# oven-controller-v3.net
KiCad netlist of a schematic drawn in EAGLE
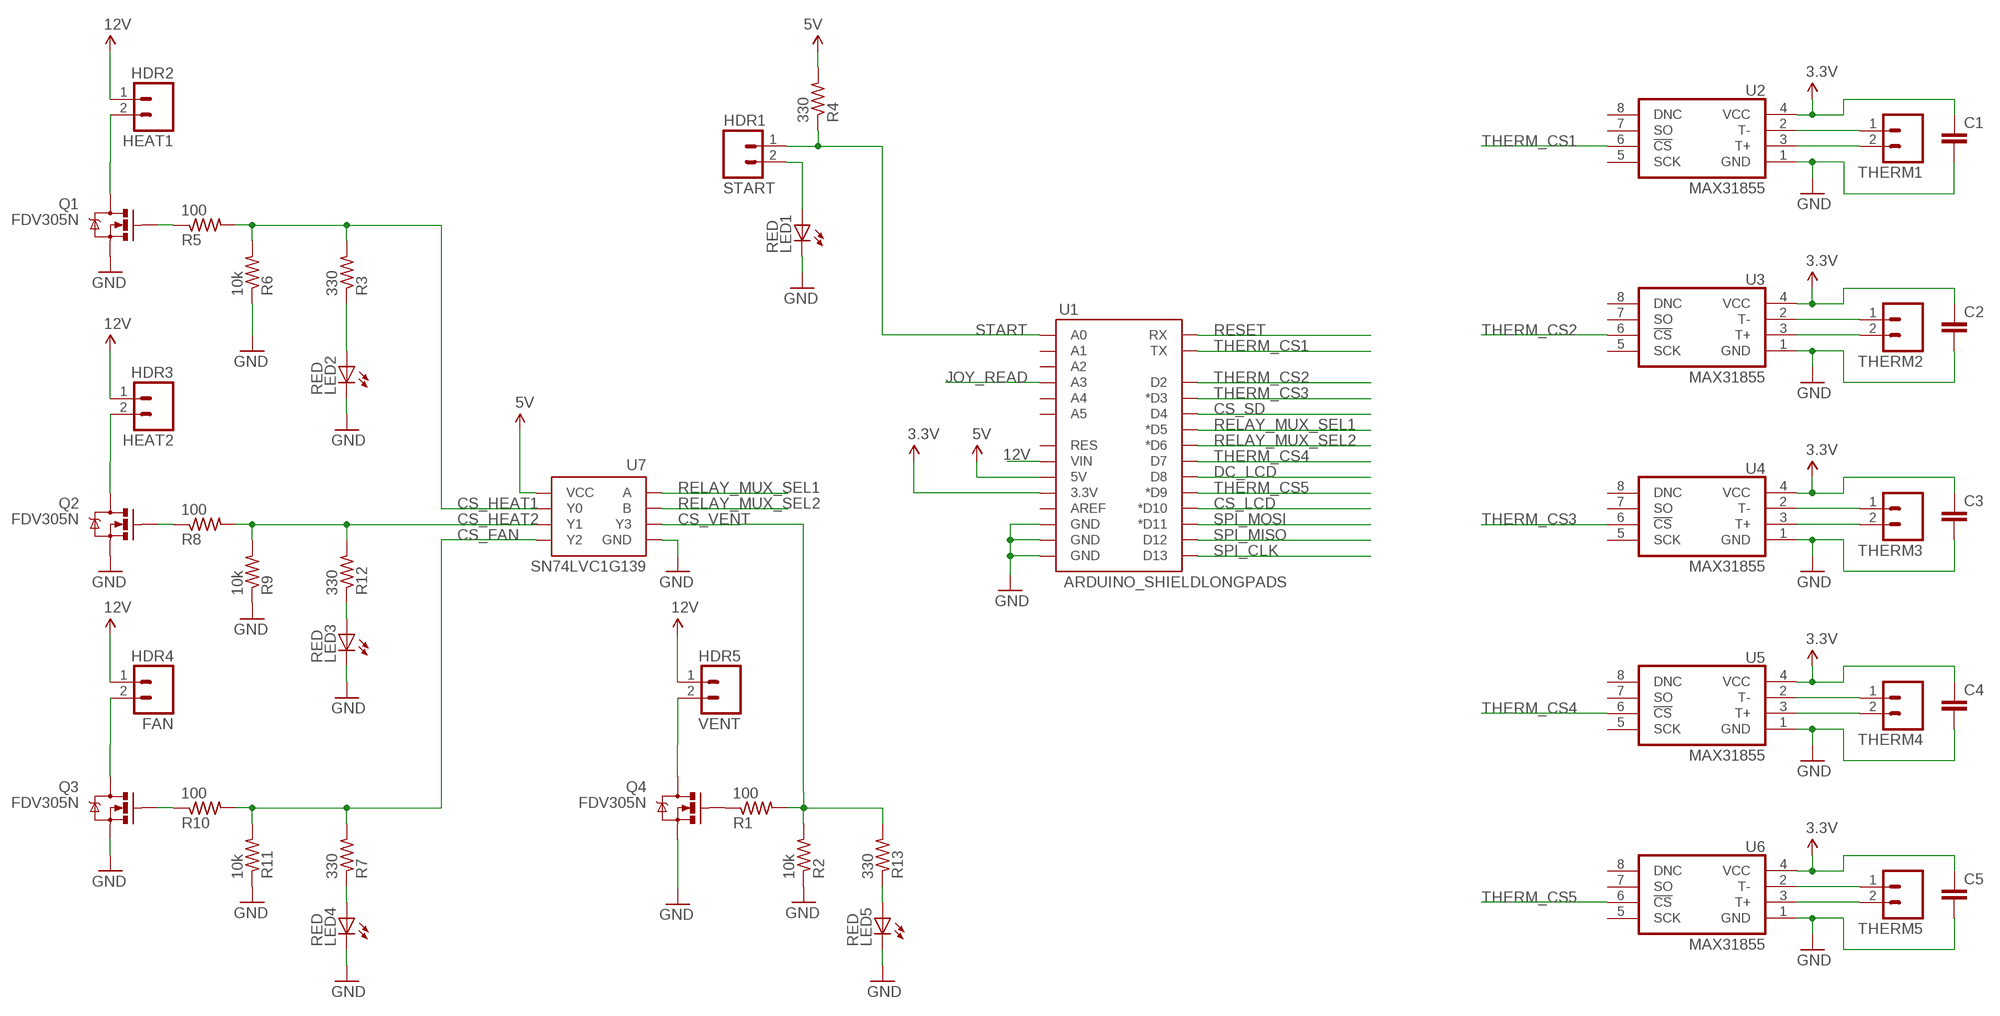
[diagram p0: schematic, sheet 1]

(export (version "E")
  (design (tool "Eeschema 10.0.6"))
  (components
    (comp (ref "C1")
      (value "C-EUC0603K")
      (footprint "eagle-import:C0603K")
      (libsource (lib "eagle-import") (part "C-EUC0603K"))
    )
    (comp (ref "C2")
      (value "C-EUC0603K")
      (footprint "eagle-import:C0603K")
      (libsource (lib "eagle-import") (part "C-EUC0603K"))
    )
    (comp (ref "C3")
      (value "C-EUC0603K")
      (footprint "eagle-import:C0603K")
      (libsource (lib "eagle-import") (part "C-EUC0603K"))
    )
    (comp (ref "C4")
      (value "C-EUC0603K")
      (footprint "eagle-import:C0603K")
      (libsource (lib "eagle-import") (part "C-EUC0603K"))
    )
    (comp (ref "C5")
      (value "C-EUC0603K")
      (footprint "eagle-import:C0603K")
      (libsource (lib "eagle-import") (part "C-EUC0603K"))
    )
    (comp (ref "FAN")
      (value "HDR4")
      (footprint "eagle-import:SCREWTERMINAL-3.5MM-2_LOCK")
      (libsource (lib "eagle-import") (part "M023.5MM_LOCK"))
    )
    (comp (ref "HEAT1")
      (value "HDR2")
      (footprint "eagle-import:SCREWTERMINAL-3.5MM-2_LOCK")
      (libsource (lib "eagle-import") (part "M023.5MM_LOCK"))
    )
    (comp (ref "HEAT2")
      (value "HDR3")
      (footprint "eagle-import:SCREWTERMINAL-3.5MM-2_LOCK")
      (libsource (lib "eagle-import") (part "M023.5MM_LOCK"))
    )
    (comp (ref "LED1")
      (value "RED")
      (footprint "eagle-import:LED-0603")
      (libsource (lib "eagle-import") (part "LED0603"))
    )
    (comp (ref "LED2")
      (value "RED")
      (footprint "eagle-import:LED-0603")
      (libsource (lib "eagle-import") (part "LED0603"))
    )
    (comp (ref "LED3")
      (value "RED")
      (footprint "eagle-import:LED-0603")
      (libsource (lib "eagle-import") (part "LED0603"))
    )
    (comp (ref "LED4")
      (value "RED")
      (footprint "eagle-import:LED-0603")
      (libsource (lib "eagle-import") (part "LED0603"))
    )
    (comp (ref "LED5")
      (value "RED")
      (footprint "eagle-import:LED-0603")
      (libsource (lib "eagle-import") (part "LED0603"))
    )
    (comp (ref "Q1")
      (value "FDV305N")
      (footprint "eagle-import:SOT23-3")
      (libsource (lib "eagle-import") (part "MOSFET-NCHANNELSMD"))
    )
    (comp (ref "Q2")
      (value "FDV305N")
      (footprint "eagle-import:SOT23-3")
      (libsource (lib "eagle-import") (part "MOSFET-NCHANNELSMD"))
    )
    (comp (ref "Q3")
      (value "FDV305N")
      (footprint "eagle-import:SOT23-3")
      (libsource (lib "eagle-import") (part "MOSFET-NCHANNELSMD"))
    )
    (comp (ref "Q4")
      (value "FDV305N")
      (footprint "eagle-import:SOT23-3")
      (libsource (lib "eagle-import") (part "MOSFET-NCHANNELSMD"))
    )
    (comp (ref "R1")
      (value "100")
      (footprint "eagle-import:0603-C-NOSILK")
      (libsource (lib "eagle-import") (part "R-US_0603-C-NOSILK"))
    )
    (comp (ref "R2")
      (value "10k")
      (footprint "eagle-import:0603-C-NOSILK")
      (libsource (lib "eagle-import") (part "R-US_0603-C-NOSILK"))
    )
    (comp (ref "R3")
      (value "330")
      (footprint "eagle-import:0603-C-NOSILK")
      (libsource (lib "eagle-import") (part "R-US_0603-C-NOSILK"))
    )
    (comp (ref "R4")
      (value "330")
      (footprint "eagle-import:0603-C-NOSILK")
      (libsource (lib "eagle-import") (part "R-US_0603-C-NOSILK"))
    )
    (comp (ref "R5")
      (value "100")
      (footprint "eagle-import:0603-C-NOSILK")
      (libsource (lib "eagle-import") (part "R-US_0603-C-NOSILK"))
    )
    (comp (ref "R6")
      (value "10k")
      (footprint "eagle-import:0603-C-NOSILK")
      (libsource (lib "eagle-import") (part "R-US_0603-C-NOSILK"))
    )
    (comp (ref "R7")
      (value "330")
      (footprint "eagle-import:0603-C-NOSILK")
      (libsource (lib "eagle-import") (part "R-US_0603-C-NOSILK"))
    )
    (comp (ref "R8")
      (value "100")
      (footprint "eagle-import:0603-C-NOSILK")
      (libsource (lib "eagle-import") (part "R-US_0603-C-NOSILK"))
    )
    (comp (ref "R9")
      (value "10k")
      (footprint "eagle-import:0603-C-NOSILK")
      (libsource (lib "eagle-import") (part "R-US_0603-C-NOSILK"))
    )
    (comp (ref "R10")
      (value "100")
      (footprint "eagle-import:0603-C-NOSILK")
      (libsource (lib "eagle-import") (part "R-US_0603-C-NOSILK"))
    )
    (comp (ref "R11")
      (value "10k")
      (footprint "eagle-import:0603-C-NOSILK")
      (libsource (lib "eagle-import") (part "R-US_0603-C-NOSILK"))
    )
    (comp (ref "R12")
      (value "330")
      (footprint "eagle-import:0603-C-NOSILK")
      (libsource (lib "eagle-import") (part "R-US_0603-C-NOSILK"))
    )
    (comp (ref "R13")
      (value "330")
      (footprint "eagle-import:0603-C-NOSILK")
      (libsource (lib "eagle-import") (part "R-US_0603-C-NOSILK"))
    )
    (comp (ref "START")
      (value "HDR1")
      (footprint "eagle-import:SCREWTERMINAL-3.5MM-2_LOCK")
      (libsource (lib "eagle-import") (part "M023.5MM_LOCK"))
    )
    (comp (ref "THERM1")
      (value "M023.5MM_LOCK")
      (footprint "eagle-import:SCREWTERMINAL-3.5MM-2_LOCK")
      (libsource (lib "eagle-import") (part "M023.5MM_LOCK"))
    )
    (comp (ref "THERM2")
      (value "M023.5MM_LOCK")
      (footprint "eagle-import:SCREWTERMINAL-3.5MM-2_LOCK")
      (libsource (lib "eagle-import") (part "M023.5MM_LOCK"))
    )
    (comp (ref "THERM3")
      (value "M023.5MM_LOCK")
      (footprint "eagle-import:SCREWTERMINAL-3.5MM-2_LOCK")
      (libsource (lib "eagle-import") (part "M023.5MM_LOCK"))
    )
    (comp (ref "THERM4")
      (value "M023.5MM_LOCK")
      (footprint "eagle-import:SCREWTERMINAL-3.5MM-2_LOCK")
      (libsource (lib "eagle-import") (part "M023.5MM_LOCK"))
    )
    (comp (ref "THERM5")
      (value "M023.5MM_LOCK")
      (footprint "eagle-import:SCREWTERMINAL-3.5MM-2_LOCK")
      (libsource (lib "eagle-import") (part "M023.5MM_LOCK"))
    )
    (comp (ref "U1")
      (value "ARDUINO_SHIELDLONGPADS")
      (footprint "eagle-import:DUEMILANOVE_SHIELD_LONGPADS")
      (libsource (lib "eagle-import") (part "ARDUINO_SHIELDLONGPADS"))
    )
    (comp (ref "U2")
      (value "MAX31855")
      (footprint "eagle-import:SO-8")
      (libsource (lib "eagle-import") (part "IC_MAX31855-SO-8"))
    )
    (comp (ref "U3")
      (value "MAX31855")
      (footprint "eagle-import:SO-8")
      (libsource (lib "eagle-import") (part "IC_MAX31855-SO-8"))
    )
    (comp (ref "U4")
      (value "MAX31855")
      (footprint "eagle-import:SO-8")
      (libsource (lib "eagle-import") (part "IC_MAX31855-SO-8"))
    )
    (comp (ref "U5")
      (value "MAX31855")
      (footprint "eagle-import:SO-8")
      (libsource (lib "eagle-import") (part "IC_MAX31855-SO-8"))
    )
    (comp (ref "U6")
      (value "MAX31855")
      (footprint "eagle-import:SO-8")
      (libsource (lib "eagle-import") (part "IC_MAX31855-SO-8"))
    )
    (comp (ref "U7")
      (value "SN74LVC1G139")
      (footprint "eagle-import:8LSSOP")
      (libsource (lib "eagle-import") (part "SN74LVC1G139"))
    )
    (comp (ref "VENT")
      (value "HDR5")
      (footprint "eagle-import:SCREWTERMINAL-3.5MM-2_LOCK")
      (libsource (lib "eagle-import") (part "M023.5MM_LOCK"))
    )
  )
  (nets
    (net (code "1") (name "/CS_FAN") (class "Default")
      (node (ref "R10") (pin "2") (pinfunction "2_2") (pintype "passive"))
      (node (ref "R11") (pin "2") (pinfunction "2_2") (pintype "passive"))
      (node (ref "R7") (pin "2") (pinfunction "2_2") (pintype "passive"))
      (node (ref "U7") (pin "P$5") (pinfunction "Y2_P$5") (pintype "bidirectional"))
    )
    (net (code "2") (name "/CS_HEAT1") (class "Default")
      (node (ref "R3") (pin "2") (pinfunction "2_2") (pintype "passive"))
      (node (ref "R5") (pin "2") (pinfunction "2_2") (pintype "passive"))
      (node (ref "R6") (pin "2") (pinfunction "2_2") (pintype "passive"))
      (node (ref "U7") (pin "P$7") (pinfunction "Y0_P$7") (pintype "power_in"))
    )
    (net (code "3") (name "/CS_HEAT2") (class "Default")
      (node (ref "R12") (pin "2") (pinfunction "2_2") (pintype "passive"))
      (node (ref "R8") (pin "2") (pinfunction "2_2") (pintype "passive"))
      (node (ref "R9") (pin "2") (pinfunction "2_2") (pintype "passive"))
      (node (ref "U7") (pin "P$6") (pinfunction "Y1_P$6") (pintype "bidirectional"))
    )
    (net (code "4") (name "/CS_LCD") (class "Default")
      (node (ref "U1") (pin "D10") (pinfunction "*D10_D10") (pintype "bidirectional"))
    )
    (net (code "5") (name "/CS_SD") (class "Default")
      (node (ref "U1") (pin "D4") (pinfunction "D4_D4") (pintype "bidirectional"))
    )
    (net (code "6") (name "/CS_VENT") (class "Default")
      (node (ref "R1") (pin "2") (pinfunction "2_2") (pintype "passive"))
      (node (ref "R13") (pin "2") (pinfunction "2_2") (pintype "passive"))
      (node (ref "R2") (pin "2") (pinfunction "2_2") (pintype "passive"))
      (node (ref "U7") (pin "P$3") (pinfunction "Y3_P$3") (pintype "bidirectional"))
    )
    (net (code "7") (name "/DC_LCD") (class "Default")
      (node (ref "U1") (pin "D8") (pinfunction "D8_D8") (pintype "bidirectional"))
    )
    (net (code "8") (name "/JOY_READ") (class "Default")
      (node (ref "U1") (pin "A3") (pinfunction "A3_A3") (pintype "bidirectional"))
    )
    (net (code "9") (name "/RELAY_MUX_SEL1") (class "Default")
      (node (ref "U1") (pin "D5") (pinfunction "*D5_D5") (pintype "bidirectional"))
      (node (ref "U7") (pin "P$1") (pinfunction "A_P$1") (pintype "bidirectional"))
    )
    (net (code "10") (name "/RELAY_MUX_SEL2") (class "Default")
      (node (ref "U1") (pin "D6") (pinfunction "*D6_D6") (pintype "bidirectional"))
      (node (ref "U7") (pin "P$2") (pinfunction "B_P$2") (pintype "power_in"))
    )
    (net (code "11") (name "/RESET") (class "Default")
      (node (ref "U1") (pin "RX") (pinfunction "RX_RX") (pintype "bidirectional"))
    )
    (net (code "12") (name "/SPI_CLK") (class "Default")
      (node (ref "U1") (pin "D13") (pinfunction "D13_D13") (pintype "bidirectional"))
    )
    (net (code "13") (name "/SPI_MISO") (class "Default")
      (node (ref "U1") (pin "D12") (pinfunction "D12_D12") (pintype "bidirectional"))
    )
    (net (code "14") (name "/SPI_MOSI") (class "Default")
      (node (ref "U1") (pin "D11") (pinfunction "*D11_D11") (pintype "bidirectional"))
    )
    (net (code "15") (name "/START") (class "Default")
      (node (ref "R4") (pin "1") (pinfunction "1_1") (pintype "passive"))
      (node (ref "START") (pin "1") (pinfunction "1_1") (pintype "passive"))
      (node (ref "U1") (pin "A0") (pinfunction "A0_A0") (pintype "bidirectional"))
    )
    (net (code "16") (name "/THERM_CS1") (class "Default")
      (node (ref "U1") (pin "TX") (pinfunction "TX_TX") (pintype "bidirectional"))
      (node (ref "U2") (pin "6") (pinfunction "~{CS}_6") (pintype "input"))
    )
    (net (code "17") (name "/THERM_CS2") (class "Default")
      (node (ref "U1") (pin "D2") (pinfunction "D2_D2") (pintype "bidirectional"))
      (node (ref "U3") (pin "6") (pinfunction "~{CS}_6") (pintype "input"))
    )
    (net (code "18") (name "/THERM_CS3") (class "Default")
      (node (ref "U1") (pin "D3") (pinfunction "*D3_D3") (pintype "bidirectional"))
      (node (ref "U4") (pin "6") (pinfunction "~{CS}_6") (pintype "input"))
    )
    (net (code "19") (name "/THERM_CS4") (class "Default")
      (node (ref "U1") (pin "D7") (pinfunction "D7_D7") (pintype "bidirectional"))
      (node (ref "U5") (pin "6") (pinfunction "~{CS}_6") (pintype "input"))
    )
    (net (code "20") (name "/THERM_CS5") (class "Default")
      (node (ref "U1") (pin "D9") (pinfunction "*D9_D9") (pintype "bidirectional"))
      (node (ref "U6") (pin "6") (pinfunction "~{CS}_6") (pintype "input"))
    )
    (net (code "21") (name "3.3V") (class "Default")
      (node (ref "C1") (pin "1") (pinfunction "1_1") (pintype "passive"))
      (node (ref "C2") (pin "1") (pinfunction "1_1") (pintype "passive"))
      (node (ref "C3") (pin "1") (pinfunction "1_1") (pintype "passive"))
      (node (ref "C4") (pin "1") (pinfunction "1_1") (pintype "passive"))
      (node (ref "C5") (pin "1") (pinfunction "1_1") (pintype "passive"))
      (node (ref "U1") (pin "3.3V") (pinfunction "3.3V_3.3V") (pintype "bidirectional"))
      (node (ref "U2") (pin "4") (pinfunction "VCC_4") (pintype "power_in"))
      (node (ref "U3") (pin "4") (pinfunction "VCC_4") (pintype "power_in"))
      (node (ref "U4") (pin "4") (pinfunction "VCC_4") (pintype "power_in"))
      (node (ref "U5") (pin "4") (pinfunction "VCC_4") (pintype "power_in"))
      (node (ref "U6") (pin "4") (pinfunction "VCC_4") (pintype "power_in"))
    )
    (net (code "22") (name "5V") (class "Default")
      (node (ref "R4") (pin "2") (pinfunction "2_2") (pintype "passive"))
      (node (ref "U1") (pin "5V") (pinfunction "5V_5V") (pintype "bidirectional"))
      (node (ref "U7") (pin "P$8") (pinfunction "VCC_P$8") (pintype "bidirectional"))
    )
    (net (code "23") (name "12V") (class "Default")
      (node (ref "FAN") (pin "1") (pinfunction "1_1") (pintype "passive"))
      (node (ref "HEAT1") (pin "1") (pinfunction "1_1") (pintype "passive"))
      (node (ref "HEAT2") (pin "1") (pinfunction "1_1") (pintype "passive"))
      (node (ref "U1") (pin "VIN") (pinfunction "VIN_VIN") (pintype "bidirectional"))
      (node (ref "VENT") (pin "1") (pinfunction "1_1") (pintype "passive"))
    )
    (net (code "24") (name "GND") (class "Default")
      (node (ref "C1") (pin "2") (pinfunction "2_2") (pintype "passive"))
      (node (ref "C2") (pin "2") (pinfunction "2_2") (pintype "passive"))
      (node (ref "C3") (pin "2") (pinfunction "2_2") (pintype "passive"))
      (node (ref "C4") (pin "2") (pinfunction "2_2") (pintype "passive"))
      (node (ref "C5") (pin "2") (pinfunction "2_2") (pintype "passive"))
      (node (ref "LED1") (pin "C") (pinfunction "C_C") (pintype "passive"))
      (node (ref "LED2") (pin "C") (pinfunction "C_C") (pintype "passive"))
      (node (ref "LED3") (pin "C") (pinfunction "C_C") (pintype "passive"))
      (node (ref "LED4") (pin "C") (pinfunction "C_C") (pintype "passive"))
      (node (ref "LED5") (pin "C") (pinfunction "C_C") (pintype "passive"))
      (node (ref "Q1") (pin "2") (pinfunction "S_2") (pintype "passive"))
      (node (ref "Q2") (pin "2") (pinfunction "S_2") (pintype "passive"))
      (node (ref "Q3") (pin "2") (pinfunction "S_2") (pintype "passive"))
      (node (ref "Q4") (pin "2") (pinfunction "S_2") (pintype "passive"))
      (node (ref "R11") (pin "1") (pinfunction "1_1") (pintype "passive"))
      (node (ref "R2") (pin "1") (pinfunction "1_1") (pintype "passive"))
      (node (ref "R6") (pin "1") (pinfunction "1_1") (pintype "passive"))
      (node (ref "R9") (pin "1") (pinfunction "1_1") (pintype "passive"))
      (node (ref "U1") (pin "GND@0") (pinfunction "GND_GND@0") (pintype "bidirectional"))
      (node (ref "U1") (pin "GND@1") (pinfunction "GND_GND@1") (pintype "bidirectional"))
      (node (ref "U1") (pin "GND@2") (pinfunction "GND_GND@2") (pintype "bidirectional"))
      (node (ref "U2") (pin "1") (pinfunction "GND_1") (pintype "power_in"))
      (node (ref "U3") (pin "1") (pinfunction "GND_1") (pintype "power_in"))
      (node (ref "U4") (pin "1") (pinfunction "GND_1") (pintype "power_in"))
      (node (ref "U5") (pin "1") (pinfunction "GND_1") (pintype "power_in"))
      (node (ref "U6") (pin "1") (pinfunction "GND_1") (pintype "power_in"))
      (node (ref "U7") (pin "P$4") (pinfunction "GND_P$4") (pintype "bidirectional"))
    )
    (net (code "25") (name "Net-(LED1-PadA)") (class "Default")
      (node (ref "LED1") (pin "A") (pinfunction "A_A") (pintype "passive"))
      (node (ref "START") (pin "2") (pinfunction "2_2") (pintype "passive"))
    )
    (net (code "26") (name "Net-(LED2-PadA)") (class "Default")
      (node (ref "LED2") (pin "A") (pinfunction "A_A") (pintype "passive"))
      (node (ref "R3") (pin "1") (pinfunction "1_1") (pintype "passive"))
    )
    (net (code "27") (name "Net-(LED3-PadA)") (class "Default")
      (node (ref "LED3") (pin "A") (pinfunction "A_A") (pintype "passive"))
      (node (ref "R12") (pin "1") (pinfunction "1_1") (pintype "passive"))
    )
    (net (code "28") (name "Net-(LED4-PadA)") (class "Default")
      (node (ref "LED4") (pin "A") (pinfunction "A_A") (pintype "passive"))
      (node (ref "R7") (pin "1") (pinfunction "1_1") (pintype "passive"))
    )
    (net (code "29") (name "Net-(LED5-PadA)") (class "Default")
      (node (ref "LED5") (pin "A") (pinfunction "A_A") (pintype "passive"))
      (node (ref "R13") (pin "1") (pinfunction "1_1") (pintype "passive"))
    )
    (net (code "30") (name "Net-(Q1-D)") (class "Default")
      (node (ref "HEAT1") (pin "2") (pinfunction "2_2") (pintype "passive"))
      (node (ref "Q1") (pin "3") (pinfunction "D_3") (pintype "passive"))
    )
    (net (code "31") (name "Net-(Q1-G)") (class "Default")
      (node (ref "Q1") (pin "1") (pinfunction "G_1") (pintype "passive"))
      (node (ref "R5") (pin "1") (pinfunction "1_1") (pintype "passive"))
    )
    (net (code "32") (name "Net-(Q2-D)") (class "Default")
      (node (ref "HEAT2") (pin "2") (pinfunction "2_2") (pintype "passive"))
      (node (ref "Q2") (pin "3") (pinfunction "D_3") (pintype "passive"))
    )
    (net (code "33") (name "Net-(Q2-G)") (class "Default")
      (node (ref "Q2") (pin "1") (pinfunction "G_1") (pintype "passive"))
      (node (ref "R8") (pin "1") (pinfunction "1_1") (pintype "passive"))
    )
    (net (code "34") (name "Net-(Q3-D)") (class "Default")
      (node (ref "FAN") (pin "2") (pinfunction "2_2") (pintype "passive"))
      (node (ref "Q3") (pin "3") (pinfunction "D_3") (pintype "passive"))
    )
    (net (code "35") (name "Net-(Q3-G)") (class "Default")
      (node (ref "Q3") (pin "1") (pinfunction "G_1") (pintype "passive"))
      (node (ref "R10") (pin "1") (pinfunction "1_1") (pintype "passive"))
    )
    (net (code "36") (name "Net-(Q4-D)") (class "Default")
      (node (ref "Q4") (pin "3") (pinfunction "D_3") (pintype "passive"))
      (node (ref "VENT") (pin "2") (pinfunction "2_2") (pintype "passive"))
    )
    (net (code "37") (name "Net-(Q4-G)") (class "Default")
      (node (ref "Q4") (pin "1") (pinfunction "G_1") (pintype "passive"))
      (node (ref "R1") (pin "1") (pinfunction "1_1") (pintype "passive"))
    )
    (net (code "38") (name "Net-(U2-T+)") (class "Default")
      (node (ref "THERM1") (pin "2") (pinfunction "2_2") (pintype "passive"))
      (node (ref "U2") (pin "3") (pinfunction "T+_3") (pintype "input"))
    )
    (net (code "39") (name "Net-(U2-T-)") (class "Default")
      (node (ref "THERM1") (pin "1") (pinfunction "1_1") (pintype "passive"))
      (node (ref "U2") (pin "2") (pinfunction "T-_2") (pintype "input"))
    )
    (net (code "40") (name "Net-(U3-T+)") (class "Default")
      (node (ref "THERM2") (pin "2") (pinfunction "2_2") (pintype "passive"))
      (node (ref "U3") (pin "3") (pinfunction "T+_3") (pintype "input"))
    )
    (net (code "41") (name "Net-(U3-T-)") (class "Default")
      (node (ref "THERM2") (pin "1") (pinfunction "1_1") (pintype "passive"))
      (node (ref "U3") (pin "2") (pinfunction "T-_2") (pintype "input"))
    )
    (net (code "42") (name "Net-(U4-T+)") (class "Default")
      (node (ref "THERM3") (pin "2") (pinfunction "2_2") (pintype "passive"))
      (node (ref "U4") (pin "3") (pinfunction "T+_3") (pintype "input"))
    )
    (net (code "43") (name "Net-(U4-T-)") (class "Default")
      (node (ref "THERM3") (pin "1") (pinfunction "1_1") (pintype "passive"))
      (node (ref "U4") (pin "2") (pinfunction "T-_2") (pintype "input"))
    )
    (net (code "44") (name "Net-(U5-T+)") (class "Default")
      (node (ref "THERM4") (pin "2") (pinfunction "2_2") (pintype "passive"))
      (node (ref "U5") (pin "3") (pinfunction "T+_3") (pintype "input"))
    )
    (net (code "45") (name "Net-(U5-T-)") (class "Default")
      (node (ref "THERM4") (pin "1") (pinfunction "1_1") (pintype "passive"))
      (node (ref "U5") (pin "2") (pinfunction "T-_2") (pintype "input"))
    )
    (net (code "46") (name "Net-(U6-T+)") (class "Default")
      (node (ref "THERM5") (pin "2") (pinfunction "2_2") (pintype "passive"))
      (node (ref "U6") (pin "3") (pinfunction "T+_3") (pintype "input"))
    )
    (net (code "47") (name "Net-(U6-T-)") (class "Default")
      (node (ref "THERM5") (pin "1") (pinfunction "1_1") (pintype "passive"))
      (node (ref "U6") (pin "2") (pinfunction "T-_2") (pintype "input"))
    )
    (net (code "48") (name "unconnected-(U1-PadA1)") (class "Default")
      (node (ref "U1") (pin "A1") (pinfunction "A1_A1") (pintype "bidirectional"))
    )
    (net (code "49") (name "unconnected-(U1-PadA2)") (class "Default")
      (node (ref "U1") (pin "A2") (pinfunction "A2_A2") (pintype "bidirectional"))
    )
    (net (code "50") (name "unconnected-(U1-PadA4)") (class "Default")
      (node (ref "U1") (pin "A4") (pinfunction "A4_A4") (pintype "bidirectional"))
    )
    (net (code "51") (name "unconnected-(U1-PadA5)") (class "Default")
      (node (ref "U1") (pin "A5") (pinfunction "A5_A5") (pintype "bidirectional"))
    )
    (net (code "52") (name "unconnected-(U1-PadAREF)") (class "Default")
      (node (ref "U1") (pin "AREF") (pinfunction "AREF_AREF") (pintype "bidirectional"))
    )
    (net (code "53") (name "unconnected-(U1-PadRES)") (class "Default")
      (node (ref "U1") (pin "RES") (pinfunction "RES_RES") (pintype "bidirectional"))
    )
    (net (code "54") (name "unconnected-(U2-DNC-Pad8)") (class "Default")
      (node (ref "U2") (pin "8") (pinfunction "DNC_8") (pintype "no_connect"))
    )
    (net (code "55") (name "unconnected-(U2-SCK-Pad5)") (class "Default")
      (node (ref "U2") (pin "5") (pinfunction "SCK_5") (pintype "input"))
    )
    (net (code "56") (name "unconnected-(U2-SO-Pad7)") (class "Default")
      (node (ref "U2") (pin "7") (pinfunction "SO_7") (pintype "output"))
    )
    (net (code "57") (name "unconnected-(U3-DNC-Pad8)") (class "Default")
      (node (ref "U3") (pin "8") (pinfunction "DNC_8") (pintype "no_connect"))
    )
    (net (code "58") (name "unconnected-(U3-SCK-Pad5)") (class "Default")
      (node (ref "U3") (pin "5") (pinfunction "SCK_5") (pintype "input"))
    )
    (net (code "59") (name "unconnected-(U3-SO-Pad7)") (class "Default")
      (node (ref "U3") (pin "7") (pinfunction "SO_7") (pintype "output"))
    )
    (net (code "60") (name "unconnected-(U4-DNC-Pad8)") (class "Default")
      (node (ref "U4") (pin "8") (pinfunction "DNC_8") (pintype "no_connect"))
    )
    (net (code "61") (name "unconnected-(U4-SCK-Pad5)") (class "Default")
      (node (ref "U4") (pin "5") (pinfunction "SCK_5") (pintype "input"))
    )
    (net (code "62") (name "unconnected-(U4-SO-Pad7)") (class "Default")
      (node (ref "U4") (pin "7") (pinfunction "SO_7") (pintype "output"))
    )
    (net (code "63") (name "unconnected-(U5-DNC-Pad8)") (class "Default")
      (node (ref "U5") (pin "8") (pinfunction "DNC_8") (pintype "no_connect"))
    )
    (net (code "64") (name "unconnected-(U5-SCK-Pad5)") (class "Default")
      (node (ref "U5") (pin "5") (pinfunction "SCK_5") (pintype "input"))
    )
    (net (code "65") (name "unconnected-(U5-SO-Pad7)") (class "Default")
      (node (ref "U5") (pin "7") (pinfunction "SO_7") (pintype "output"))
    )
    (net (code "66") (name "unconnected-(U6-DNC-Pad8)") (class "Default")
      (node (ref "U6") (pin "8") (pinfunction "DNC_8") (pintype "no_connect"))
    )
    (net (code "67") (name "unconnected-(U6-SCK-Pad5)") (class "Default")
      (node (ref "U6") (pin "5") (pinfunction "SCK_5") (pintype "input"))
    )
    (net (code "68") (name "unconnected-(U6-SO-Pad7)") (class "Default")
      (node (ref "U6") (pin "7") (pinfunction "SO_7") (pintype "output"))
    )
  )
)
